# main.net
KiCad netlist of a schematic drawn in Altium Designer
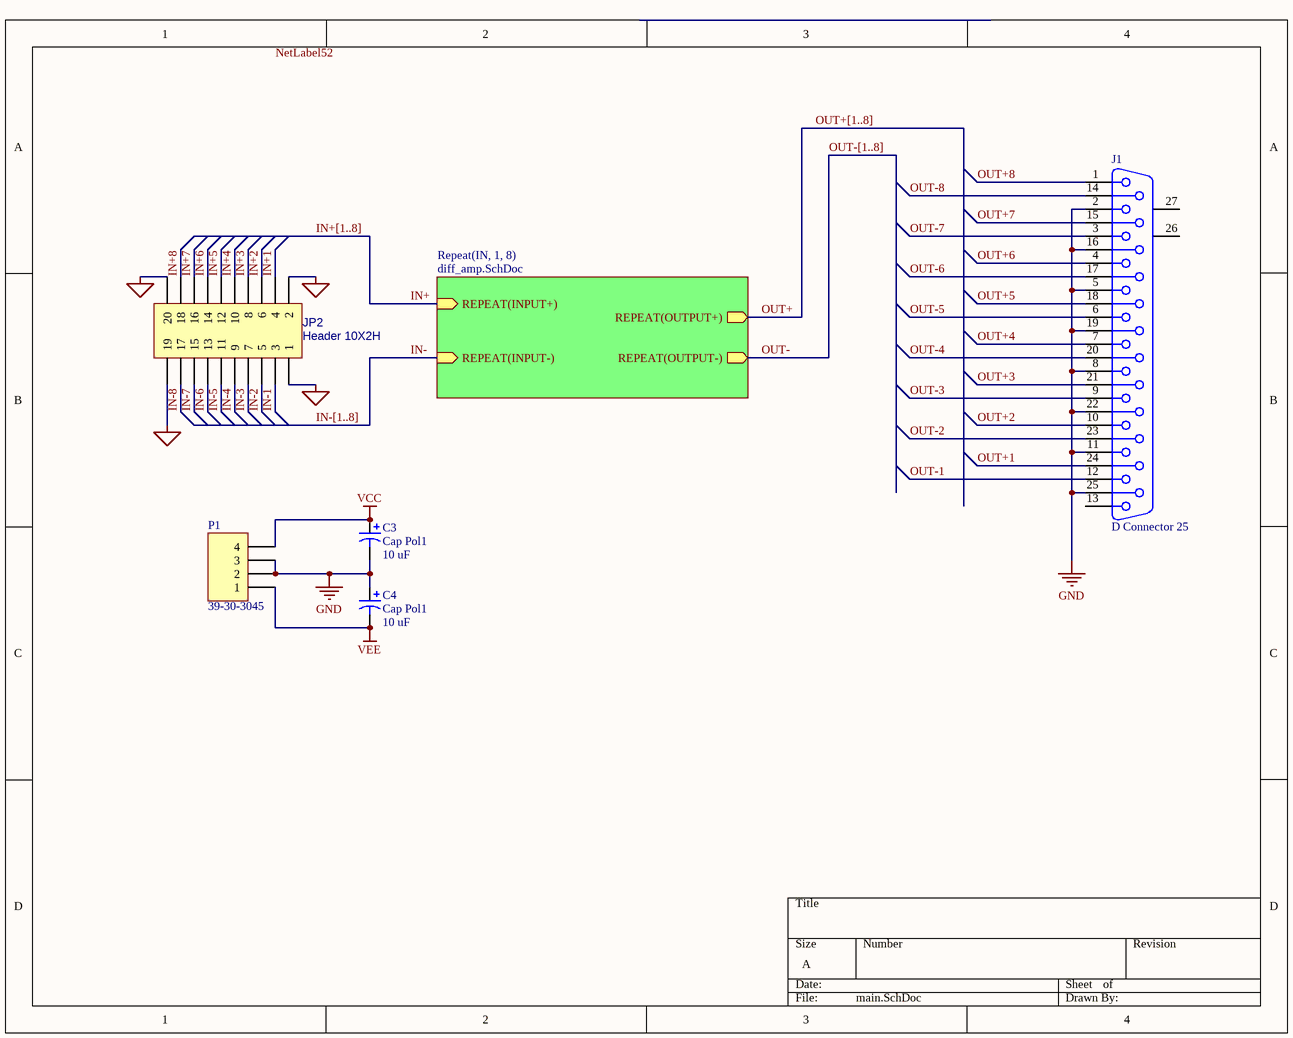
[diagram p0: main.SchDoc]

(export (version "E")
  (design (tool "Eeschema 10.0.6"))
  (components
    (comp (ref "C3")
      (value "Cap Pol1")
      (footprint "CAPPR5-5x5")
      (description "Polarized Capacitor (Radial)")
      (fields (field (name "ALTIUM_VALUE") "10 uF") (field (name "PUBLISHER") "Altium Limited"))
      (libsource (lib "Miscellaneous Devices") (part "Cap Pol1"))
    )
    (comp (ref "C4")
      (value "Cap Pol1")
      (footprint "CAPPR5-5x5")
      (description "Polarized Capacitor (Radial)")
      (fields (field (name "ALTIUM_VALUE") "10 uF") (field (name "PUBLISHER") "Altium Limited"))
      (libsource (lib "Miscellaneous Devices") (part "Cap Pol1"))
    )
    (comp (ref "J1")
      (value "D Connector 25")
      (footprint "DSUB1.385-2H25A")
      (description "Receptacle Assembly, 25 Position, Right Angle")
      (fields (field (name "PUBLISHER") "Altium Limited"))
      (libsource (lib "Miscellaneous Connectors") (part "D Connector 25"))
    )
    (comp (ref "JP2")
      (value "Header 10X2H")
      (footprint "HDR2X10")
      (description "Header, 10-Pin, Dual row, Right Angle")
      (fields (field (name "MANUFACTURER") "Generic Components") (field (name "PUBLISHER") "Altium Limited"))
      (libsource (lib "Miscellaneous Connectors") (part "Header 10X2H"))
    )
    (comp (ref "P1")
      (value "39-30-3045")
      (footprint "MJ4RTHR")
      (description "Header, 4-Pin")
      (fields (field (name "PUBLISHER") "Altium Limited"))
      (libsource (lib "Miscellaneous Connectors") (part "Header 4"))
    )
  )
  (nets
    (net (code "2") (name "/IN+1") (class "Default")
      (node (ref "JP2") (pin "4") (pinfunction "4_4") (pintype "passive"))
    )
    (net (code "3") (name "/IN+2") (class "Default")
      (node (ref "JP2") (pin "6") (pinfunction "6_6") (pintype "passive"))
    )
    (net (code "4") (name "/IN+3") (class "Default")
      (node (ref "JP2") (pin "8") (pinfunction "8_8") (pintype "passive"))
    )
    (net (code "5") (name "/IN+4") (class "Default")
      (node (ref "JP2") (pin "10") (pinfunction "10_10") (pintype "passive"))
    )
    (net (code "6") (name "/IN+5") (class "Default")
      (node (ref "JP2") (pin "12") (pinfunction "12_12") (pintype "passive"))
    )
    (net (code "7") (name "/IN+6") (class "Default")
      (node (ref "JP2") (pin "14") (pinfunction "14_14") (pintype "passive"))
    )
    (net (code "8") (name "/IN+7") (class "Default")
      (node (ref "JP2") (pin "16") (pinfunction "16_16") (pintype "passive"))
    )
    (net (code "9") (name "/IN+8") (class "Default")
      (node (ref "JP2") (pin "18") (pinfunction "18_18") (pintype "passive"))
    )
    (net (code "12") (name "/IN-1") (class "Default")
      (node (ref "JP2") (pin "3") (pinfunction "3_3") (pintype "passive"))
    )
    (net (code "13") (name "/IN-2") (class "Default")
      (node (ref "JP2") (pin "5") (pinfunction "5_5") (pintype "passive"))
    )
    (net (code "14") (name "/IN-3") (class "Default")
      (node (ref "JP2") (pin "7") (pinfunction "7_7") (pintype "passive"))
    )
    (net (code "15") (name "/IN-4") (class "Default")
      (node (ref "JP2") (pin "9") (pinfunction "9_9") (pintype "passive"))
    )
    (net (code "16") (name "/IN-5") (class "Default")
      (node (ref "JP2") (pin "11") (pinfunction "11_11") (pintype "passive"))
    )
    (net (code "17") (name "/IN-6") (class "Default")
      (node (ref "JP2") (pin "13") (pinfunction "13_13") (pintype "passive"))
    )
    (net (code "18") (name "/IN-7") (class "Default")
      (node (ref "JP2") (pin "15") (pinfunction "15_15") (pintype "passive"))
    )
    (net (code "19") (name "/IN-8") (class "Default")
      (node (ref "JP2") (pin "17") (pinfunction "17_17") (pintype "passive"))
    )
    (net (code "23") (name "/OUT+1") (class "Default")
      (node (ref "J1") (pin "24") (pinfunction "24_24") (pintype "passive"))
    )
    (net (code "24") (name "/OUT+2") (class "Default")
      (node (ref "J1") (pin "10") (pinfunction "10_10") (pintype "passive"))
    )
    (net (code "25") (name "/OUT+3") (class "Default")
      (node (ref "J1") (pin "21") (pinfunction "21_21") (pintype "passive"))
    )
    (net (code "26") (name "/OUT+4") (class "Default")
      (node (ref "J1") (pin "7") (pinfunction "7_7") (pintype "passive"))
    )
    (net (code "27") (name "/OUT+5") (class "Default")
      (node (ref "J1") (pin "18") (pinfunction "18_18") (pintype "passive"))
    )
    (net (code "28") (name "/OUT+6") (class "Default")
      (node (ref "J1") (pin "4") (pinfunction "4_4") (pintype "passive"))
    )
    (net (code "29") (name "/OUT+7") (class "Default")
      (node (ref "J1") (pin "15") (pinfunction "15_15") (pintype "passive"))
    )
    (net (code "30") (name "/OUT+8") (class "Default")
      (node (ref "J1") (pin "1") (pinfunction "1_1") (pintype "passive"))
    )
    (net (code "33") (name "/OUT-1") (class "Default")
      (node (ref "J1") (pin "12") (pinfunction "12_12") (pintype "passive"))
    )
    (net (code "34") (name "/OUT-2") (class "Default")
      (node (ref "J1") (pin "23") (pinfunction "23_23") (pintype "passive"))
    )
    (net (code "35") (name "/OUT-3") (class "Default")
      (node (ref "J1") (pin "9") (pinfunction "9_9") (pintype "passive"))
    )
    (net (code "36") (name "/OUT-4") (class "Default")
      (node (ref "J1") (pin "20") (pinfunction "20_20") (pintype "passive"))
    )
    (net (code "37") (name "/OUT-5") (class "Default")
      (node (ref "J1") (pin "6") (pinfunction "6_6") (pintype "passive"))
    )
    (net (code "38") (name "/OUT-6") (class "Default")
      (node (ref "J1") (pin "17") (pinfunction "17_17") (pintype "passive"))
    )
    (net (code "39") (name "/OUT-7") (class "Default")
      (node (ref "J1") (pin "3") (pinfunction "3_3") (pintype "passive"))
    )
    (net (code "40") (name "/OUT-8") (class "Default")
      (node (ref "J1") (pin "14") (pinfunction "14_14") (pintype "passive"))
    )
    (net (code "42") (name "AGND") (class "Default")
      (node (ref "JP2") (pin "1") (pinfunction "1_1") (pintype "passive"))
      (node (ref "JP2") (pin "19") (pinfunction "19_19") (pintype "passive"))
      (node (ref "JP2") (pin "2") (pinfunction "2_2") (pintype "passive"))
      (node (ref "JP2") (pin "20") (pinfunction "20_20") (pintype "passive"))
    )
    (net (code "43") (name "GND") (class "Default")
      (node (ref "C3") (pin "2") (pinfunction "2_2") (pintype "passive"))
      (node (ref "C4") (pin "1") (pinfunction "1_1") (pintype "passive"))
      (node (ref "J1") (pin "11") (pinfunction "11_11") (pintype "passive"))
      (node (ref "J1") (pin "16") (pinfunction "16_16") (pintype "passive"))
      (node (ref "J1") (pin "19") (pinfunction "19_19") (pintype "passive"))
      (node (ref "J1") (pin "2") (pinfunction "2_2") (pintype "passive"))
      (node (ref "J1") (pin "22") (pinfunction "22_22") (pintype "passive"))
      (node (ref "J1") (pin "25") (pinfunction "25_25") (pintype "passive"))
      (node (ref "J1") (pin "5") (pinfunction "5_5") (pintype "passive"))
      (node (ref "J1") (pin "8") (pinfunction "8_8") (pintype "passive"))
      (node (ref "P1") (pin "2") (pinfunction "2_2") (pintype "passive"))
      (node (ref "P1") (pin "3") (pinfunction "3_3") (pintype "passive"))
    )
    (net (code "44") (name "VCC") (class "Default")
      (node (ref "C3") (pin "1") (pinfunction "1_1") (pintype "passive"))
      (node (ref "P1") (pin "4") (pinfunction "4_4") (pintype "passive"))
    )
    (net (code "45") (name "VEE") (class "Default")
      (node (ref "C4") (pin "2") (pinfunction "2_2") (pintype "passive"))
      (node (ref "P1") (pin "1") (pinfunction "1_1") (pintype "passive"))
    )
    (net (code "46") (name "unconnected-(J1-MH1-Pad26)") (class "Default")
      (node (ref "J1") (pin "26") (pinfunction "MH1_26") (pintype "passive"))
    )
    (net (code "47") (name "unconnected-(J1-MH2-Pad27)") (class "Default")
      (node (ref "J1") (pin "27") (pinfunction "MH2_27") (pintype "passive"))
    )
    (net (code "48") (name "unconnected-(J1-Pad13)") (class "Default")
      (node (ref "J1") (pin "13") (pinfunction "13_13") (pintype "passive"))
    )
  )
)
